# NLOS_PCB.net
KiCad netlist of a schematic drawn in Altium Designer
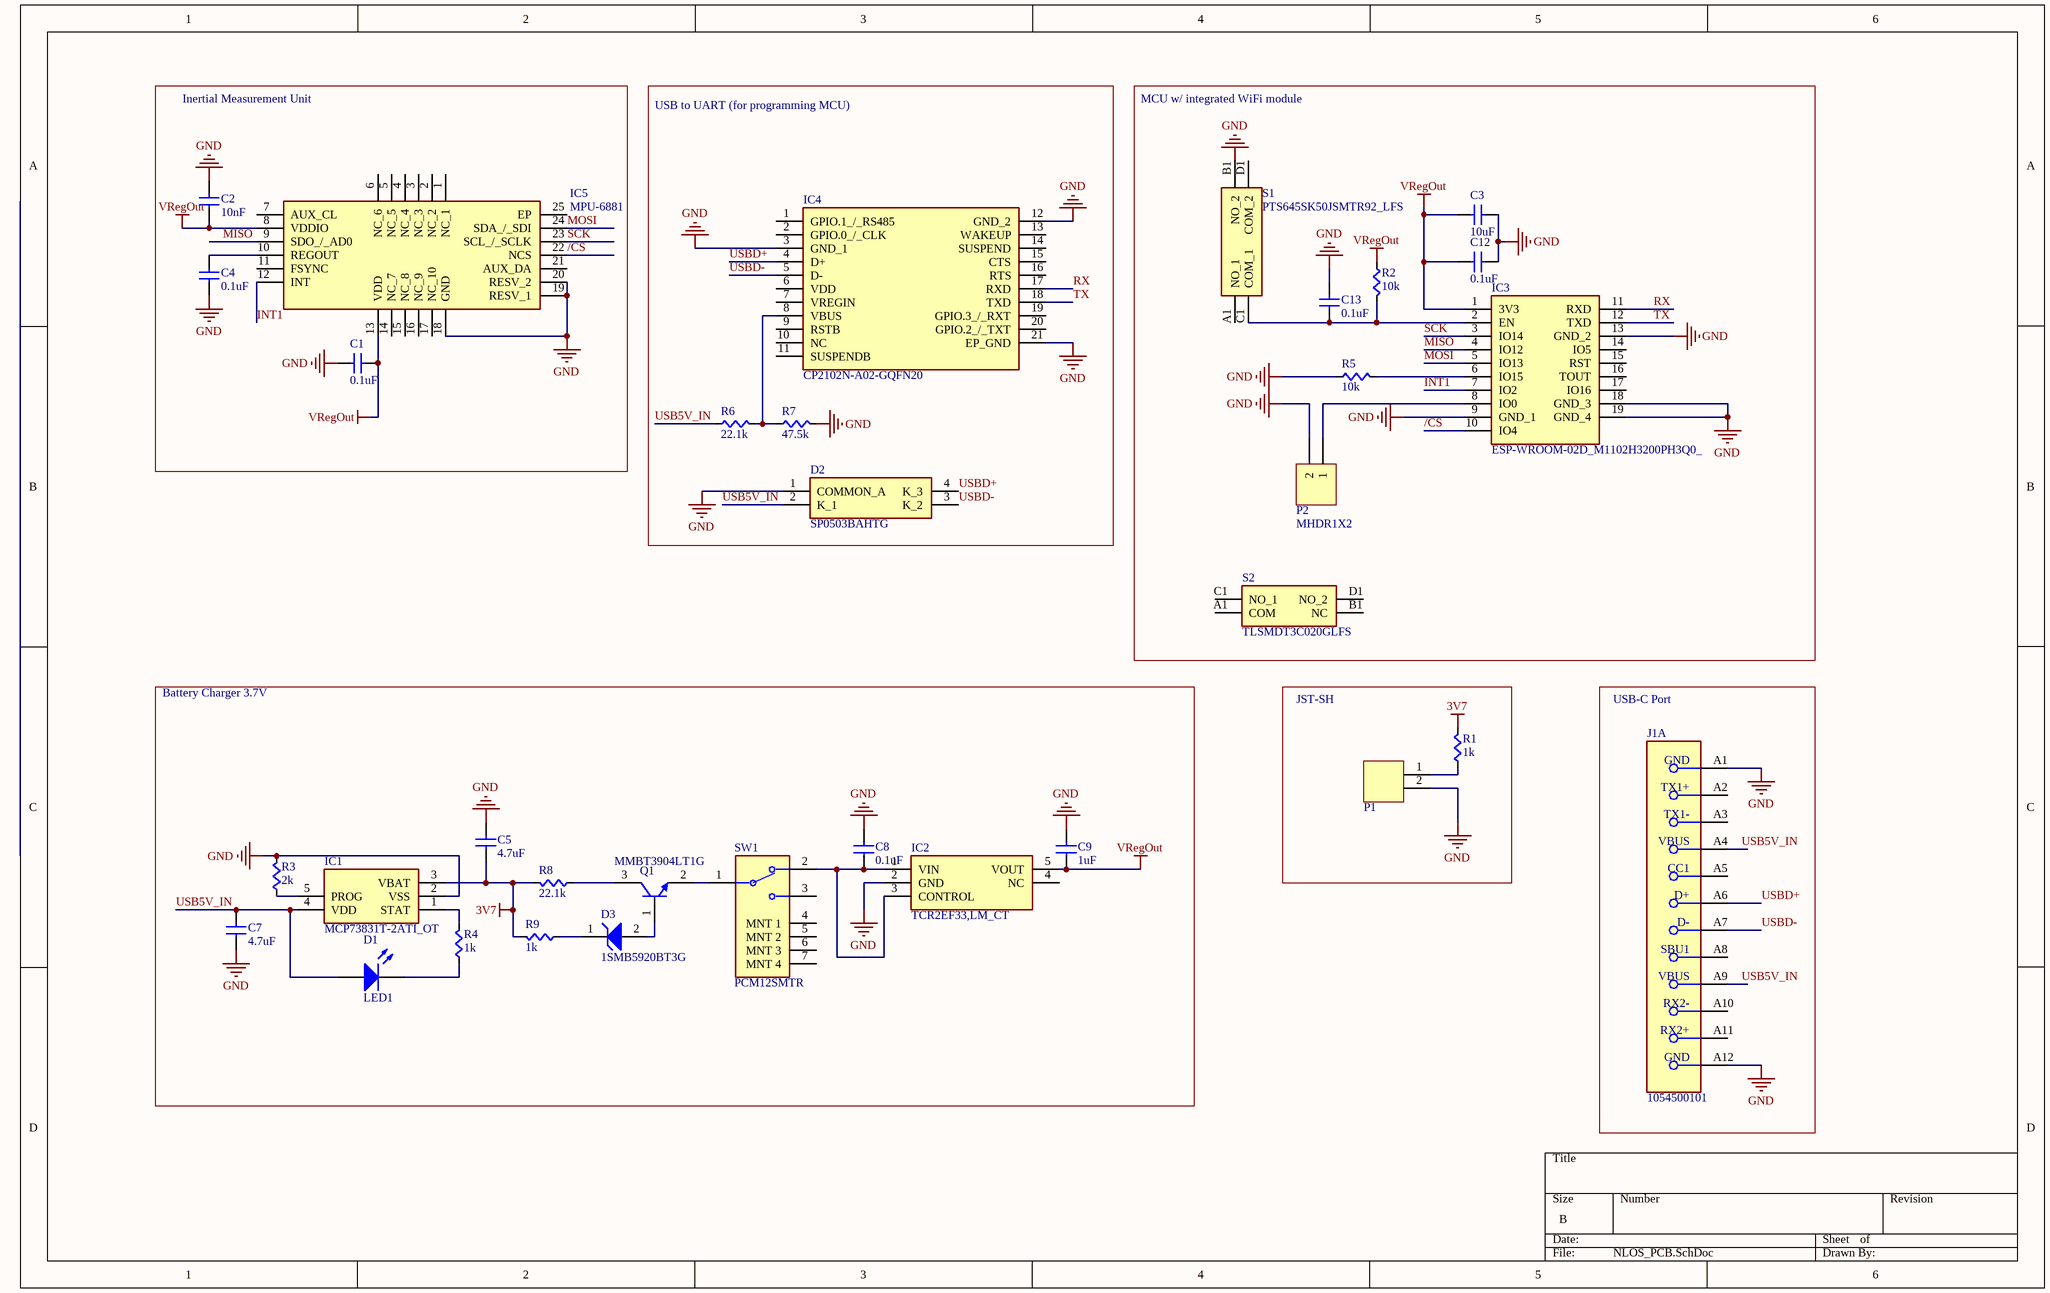
[diagram p0: NLOS_PCB.SchDoc]

(export (version "E")
  (design (tool "Eeschema 10.0.6"))
  (components
    (comp (ref "C1")
      (value "0.1uF")
      (footprint "CAPC0603")
      (fields (field (name "Comment") "Cap"))
      (libsource (lib "Passives") (part "Cap"))
    )
    (comp (ref "C2")
      (value "10nF")
      (footprint "CAPC0603")
      (fields (field (name "Comment") "Cap"))
      (libsource (lib "Passives") (part "Cap"))
    )
    (comp (ref "C3")
      (value "10uF")
      (footprint "CAPC0603")
      (fields (field (name "Comment") "Cap"))
      (libsource (lib "Passives") (part "Cap"))
    )
    (comp (ref "C4")
      (value "0.1uF")
      (footprint "CAPC0603")
      (fields (field (name "Comment") "Cap"))
      (libsource (lib "Passives") (part "Cap"))
    )
    (comp (ref "C5")
      (value "4.7uF")
      (footprint "CAPC0603")
      (fields (field (name "Comment") "Cap"))
      (libsource (lib "Passives") (part "Cap"))
    )
    (comp (ref "C7")
      (value "4.7uF")
      (footprint "CAPC0603")
      (fields (field (name "Comment") "Cap"))
      (libsource (lib "Passives") (part "Cap"))
    )
    (comp (ref "C8")
      (value "0.1uF")
      (footprint "CAPC0603")
      (fields (field (name "Comment") "Cap"))
      (libsource (lib "Passives") (part "Cap"))
    )
    (comp (ref "C9")
      (value "1uF")
      (footprint "CAPC0603")
      (fields (field (name "Comment") "Cap"))
      (libsource (lib "Passives") (part "Cap"))
    )
    (comp (ref "C12")
      (value "0.1uF")
      (footprint "CAPC0603")
      (fields (field (name "Comment") "Cap"))
      (libsource (lib "Passives") (part "Cap"))
    )
    (comp (ref "C13")
      (value "0.1uF")
      (footprint "CAPC0603")
      (fields (field (name "Comment") "Cap"))
      (libsource (lib "Passives") (part "Cap"))
    )
    (comp (ref "D1")
      (value "LED1")
      (footprint "LED-1")
      (description "Typical RED GaAs LED")
      (fields (field (name "PUBLISHER") "Altium Limited"))
      (libsource (lib "Miscellaneous Devices") (part "LED1"))
    )
    (comp (ref "D2")
      (value "SP0503BAHTG")
      (footprint "SamacSys:SP0503BAHTG")
      (description "TVS Diode (Uni-directional)")
      (fields (field (name "MOUSER PART NUMBER") "576-SP0503BAHTG"))
      (libsource (lib "*") (part "SP0503BAHTG"))
    )
    (comp (ref "D3")
      (value "1SMB5920BT3G")
      (footprint "ONSC-SMB-2-403A-03_H_V")
      (description "3 W Zener Voltage Regulator, 2-Pin SMB, Pb-Free, Tape and Reel")
      (fields (field (name "MANUFACTURER") "On Semiconductor"))
      (libsource (lib "Altium Content Vault") (part "ONSC-K1A2-2"))
    )
    (comp (ref "IC1")
      (value "MCP73831T-2ATI_OT")
      (footprint "SamacSys:SOT95P270X145-5N")
      (description "Integrated Circuit")
      (fields
        (field (name "MOUSER2 PART NUMBER") "579-MCP73831T-2ATIOT")
        (field (name "MANUFACTURER_PART_NUMBER") "MCP73831T-2ATI/OT")
      )
      (libsource (lib "*") (part "MCP73831T-2ATI_OT"))
    )
    (comp (ref "IC2")
      (value "TCR2EF33,LM_CT")
      (footprint "SamacSys:SOT-25")
      (description "Integrated Circuit")
      (fields
        (field (name "MOUSER2 PART NUMBER") "757-TCR2EF33LMCT")
        (field (name "MANUFACTURER_PART_NUMBER") "TCR2EF33,LM(CT")
      )
      (libsource (lib "*") (part "TCR2EF33,LM_CT"))
    )
    (comp (ref "IC3")
      (value "ESP-WROOM-02D_M1102H3200PH3Q0_")
      (footprint "SamacSys:ESPWROOM02DM1102H3200PH3Q0")
      (description "Integrated Circuit")
      (fields
        (field (name "MANUFACTURER_PART_NUMBER") "ESP-WROOM-02D(M1102H3200PH3Q0)")
        (field (name "MOUSER PART NUMBER") "356-ESPWROOM02D(4MB)")
      )
      (libsource (lib "*") (part "ESP-WROOM-02D_M1102H3200PH3Q0_"))
    )
    (comp (ref "IC4")
      (value "CP2102N-A02-GQFN20")
      (footprint "SamacSys:CP2102NA02GQFN20")
      (description "Integrated Circuit")
      (fields (field (name "MOUSER PART NUMBER") "634-CP2102NA02GQFN20"))
      (libsource (lib "*") (part "CP2102N-A02-GQFN20"))
    )
    (comp (ref "IC5")
      (value "MPU-6881")
      (footprint "SamacSys:QFN40P300X300X95-25N-D")
      (description "Integrated Circuit")
      (fields (field (name "MOUSER PART NUMBER") "410-MPU-6881"))
      (libsource (lib "*") (part "MPU-6881"))
    )
    (comp (ref "J1")
      (value "1054500101")
      (footprint "FP-1054500101-MFG")
      (description "CONN RCP USB3.1 TYPEC 24P SMD RA")
      (fields
        (field (name "MANUFACTURER") "Molex")
        (field (name "OCTOPART") "https://octopart.com/105450-0101-molex-68082325")
      )
      (libsource (lib "Altium Content Vault") (part "9808b19ecaf079fb99eed69f0495cd0"))
    )
    (comp (ref "P1")
      (value "2-pin Horz Sherlock")
      (footprint "MOLEX-HDR-1X2-SHERLOCK-HORZ")
      (fields
        (field (name "MANUFACTURER PART NUMBER") "0353630260")
        (field (name "MANUFACTURER") "Molex Inc")
      )
      (libsource (lib "Connectors") (part "MOLEX-HDR-1x2-SHERLOCK_RA"))
    )
    (comp (ref "P2")
      (value "MHDR1X2")
      (footprint "MHDR1X2")
      (description "Header, 2-Pin")
      (fields (field (name "PUBLISHER") "Altium Limited"))
      (libsource (lib "Miscellaneous Connectors") (part "MHDR1X2"))
    )
    (comp (ref "Q1")
      (value "MMBT3904LT1G")
      (footprint "ONSC-SOT-23-3-318-08_V")
      (description "General Purpose Transistor, NPN Silicon, 3-Pin SOT-23, Pb-Free, Tape and Reel")
      (fields (field (name "MANUFACTURER") "On Semiconductor"))
      (libsource (lib "Altium Content Vault") (part "ONSC-NPN-B1E2C3-3"))
    )
    (comp (ref "R1")
      (value "1k")
      (footprint "RES0603")
      (fields (field (name "Comment") "Res"))
      (libsource (lib "Passives") (part "Res"))
    )
    (comp (ref "R2")
      (value "10k")
      (footprint "RES0603")
      (fields (field (name "Comment") "Res"))
      (libsource (lib "Passives") (part "Res"))
    )
    (comp (ref "R3")
      (value "2k")
      (footprint "RES0603")
      (fields (field (name "Comment") "Res"))
      (libsource (lib "Passives") (part "Res"))
    )
    (comp (ref "R4")
      (value "1k")
      (footprint "RES0603")
      (fields (field (name "Comment") "Res"))
      (libsource (lib "Passives") (part "Res"))
    )
    (comp (ref "R5")
      (value "10k")
      (footprint "RES0603")
      (fields (field (name "Comment") "Res"))
      (libsource (lib "Passives") (part "Res"))
    )
    (comp (ref "R6")
      (value "22.1k")
      (footprint "RES0603")
      (fields (field (name "Comment") "Res"))
      (libsource (lib "Passives") (part "Res"))
    )
    (comp (ref "R7")
      (value "47.5k")
      (footprint "RES0603")
      (fields (field (name "Comment") "Res"))
      (libsource (lib "Passives") (part "Res"))
    )
    (comp (ref "R8")
      (value "22.1k")
      (footprint "RES0603")
      (fields (field (name "Comment") "Res"))
      (libsource (lib "Passives") (part "Res"))
    )
    (comp (ref "R9")
      (value "1k")
      (footprint "RES0603")
      (fields (field (name "Comment") "Res"))
      (libsource (lib "Passives") (part "Res"))
    )
    (comp (ref "S1")
      (value "PTS645SK50JSMTR92_LFS")
      (footprint "SamacSys:PTS645SK50JSMTR92LFS")
      (description "Switch")
      (fields
        (field (name "MANUFACTURER_PART_NUMBER") "PTS645SK50JSMTR92 LFS")
        (field (name "MOUSER PART NUMBER") "611-SK50JSMTR92LFS")
      )
      (libsource (lib "*") (part "PTS645SK50JSMTR92_LFS"))
    )
    (comp (ref "S2")
      (value "TLSMDT3C020GLFS")
      (footprint "SamacSys:TLSMDT3C020GLFS")
      (description "Tactile Switches 6x6.1x3.45mm Tactile Switch")
      (fields (field (name "MOUSER PART NUMBER") "611-TLSMDT3C020GLFS"))
      (libsource (lib "SamacSys") (part "TLSMDT3C020GLFS"))
    )
    (comp (ref "SW1")
      (value "PCM12SMTR")
      (footprint "FP-PCM12SMTR-MFG")
      (description "SWITCH SLIDE SPDT 300MA 6V")
      (libsource (lib "Altium Content Vault") (part "1a3f67d7e2b5469b171eeab59ffb4d2"))
    )
  )
  (nets
    (net (code "1") (name "/INT1") (class "Default")
      (node (ref "IC3") (pin "7") (pinfunction "IO2_7") (pintype "passive"))
      (node (ref "IC5") (pin "12") (pinfunction "INT_12") (pintype "passive"))
    )
    (net (code "2") (name "/MISO") (class "Default")
      (node (ref "IC3") (pin "4") (pinfunction "IO12_4") (pintype "passive"))
      (node (ref "IC5") (pin "9") (pinfunction "SDO_/_AD0_9") (pintype "passive"))
    )
    (net (code "3") (name "/MOSI") (class "Default")
      (node (ref "IC3") (pin "5") (pinfunction "IO13_5") (pintype "passive"))
      (node (ref "IC5") (pin "24") (pinfunction "SDA_/_SDI_24") (pintype "passive"))
    )
    (net (code "4") (name "/RX") (class "Default")
      (node (ref "IC3") (pin "11") (pinfunction "RXD_11") (pintype "passive"))
      (node (ref "IC4") (pin "17") (pinfunction "RXD_17") (pintype "passive"))
    )
    (net (code "5") (name "/SCK") (class "Default")
      (node (ref "IC3") (pin "3") (pinfunction "IO14_3") (pintype "passive"))
      (node (ref "IC5") (pin "23") (pinfunction "SCL_/_SCLK_23") (pintype "passive"))
    )
    (net (code "6") (name "/TX") (class "Default")
      (node (ref "IC3") (pin "12") (pinfunction "TXD_12") (pintype "passive"))
      (node (ref "IC4") (pin "18") (pinfunction "TXD_18") (pintype "passive"))
    )
    (net (code "7") (name "/USB5V_IN") (class "Default")
      (node (ref "C7") (pin "2") (pinfunction "B_2") (pintype "passive"))
      (node (ref "D1") (pin "1") (pinfunction "A_1") (pintype "passive"))
      (node (ref "D2") (pin "2") (pinfunction "K_1_2") (pintype "passive"))
      (node (ref "IC1") (pin "4") (pinfunction "VDD_4") (pintype "power_in"))
      (node (ref "J1") (pin "A4") (pinfunction "VBUS_A4") (pintype "passive"))
      (node (ref "J1") (pin "A9") (pinfunction "VBUS_A9") (pintype "passive"))
      (node (ref "R6") (pin "2") (pinfunction "B_2") (pintype "passive"))
    )
    (net (code "8") (name "/USBD+") (class "Default")
      (node (ref "D2") (pin "4") (pinfunction "K_3_4") (pintype "passive"))
      (node (ref "IC4") (pin "4") (pinfunction "D+_4") (pintype "passive"))
      (node (ref "J1") (pin "A6") (pinfunction "D+_A6") (pintype "passive"))
    )
    (net (code "9") (name "/USBD-") (class "Default")
      (node (ref "D2") (pin "3") (pinfunction "K_2_3") (pintype "passive"))
      (node (ref "IC4") (pin "5") (pinfunction "D-_5") (pintype "passive"))
      (node (ref "J1") (pin "A7") (pinfunction "D-_A7") (pintype "passive"))
    )
    (net (code "10") (name "/{slash}CS") (class "Default")
      (node (ref "IC3") (pin "10") (pinfunction "IO4_10") (pintype "passive"))
      (node (ref "IC5") (pin "22") (pinfunction "NCS_22") (pintype "passive"))
    )
    (net (code "11") (name "3V7") (class "Default")
      (node (ref "C5") (pin "2") (pinfunction "B_2") (pintype "passive"))
      (node (ref "IC1") (pin "3") (pinfunction "VBAT_3") (pintype "passive"))
      (node (ref "R1") (pin "1") (pinfunction "A_1") (pintype "passive"))
      (node (ref "R8") (pin "1") (pinfunction "A_1") (pintype "passive"))
      (node (ref "R9") (pin "1") (pinfunction "A_1") (pintype "passive"))
    )
    (net (code "12") (name "GND") (class "Default")
      (node (ref "C1") (pin "2") (pinfunction "B_2") (pintype "passive"))
      (node (ref "C12") (pin "1") (pinfunction "A_1") (pintype "passive"))
      (node (ref "C13") (pin "2") (pinfunction "B_2") (pintype "passive"))
      (node (ref "C2") (pin "2") (pinfunction "B_2") (pintype "passive"))
      (node (ref "C3") (pin "1") (pinfunction "A_1") (pintype "passive"))
      (node (ref "C4") (pin "1") (pinfunction "A_1") (pintype "passive"))
      (node (ref "C5") (pin "1") (pinfunction "A_1") (pintype "passive"))
      (node (ref "C7") (pin "1") (pinfunction "A_1") (pintype "passive"))
      (node (ref "C8") (pin "2") (pinfunction "B_2") (pintype "passive"))
      (node (ref "C9") (pin "2") (pinfunction "B_2") (pintype "passive"))
      (node (ref "D2") (pin "1") (pinfunction "COMMON_A_1") (pintype "passive"))
      (node (ref "IC1") (pin "2") (pinfunction "VSS_2") (pintype "power_in"))
      (node (ref "IC2") (pin "2") (pinfunction "GND_2") (pintype "passive"))
      (node (ref "IC3") (pin "13") (pinfunction "GND_2_13") (pintype "passive"))
      (node (ref "IC3") (pin "18") (pinfunction "GND_3_18") (pintype "passive"))
      (node (ref "IC3") (pin "19") (pinfunction "GND_4_19") (pintype "passive"))
      (node (ref "IC3") (pin "9") (pinfunction "GND_1_9") (pintype "passive"))
      (node (ref "IC4") (pin "12") (pinfunction "GND_2_12") (pintype "passive"))
      (node (ref "IC4") (pin "21") (pinfunction "EP_GND_21") (pintype "passive"))
      (node (ref "IC4") (pin "3") (pinfunction "GND_1_3") (pintype "passive"))
      (node (ref "IC5") (pin "18") (pinfunction "GND_18") (pintype "passive"))
      (node (ref "IC5") (pin "19") (pinfunction "RESV_1_19") (pintype "passive"))
      (node (ref "IC5") (pin "20") (pinfunction "RESV_2_20") (pintype "passive"))
      (node (ref "J1") (pin "A1") (pinfunction "GND_A1") (pintype "passive"))
      (node (ref "J1") (pin "A12") (pinfunction "GND_A12") (pintype "passive"))
      (node (ref "P1") (pin "2") (pinfunction "2_2") (pintype "passive"))
      (node (ref "P2") (pin "2") (pinfunction "2_2") (pintype "passive"))
      (node (ref "R3") (pin "1") (pinfunction "A_1") (pintype "passive"))
      (node (ref "R5") (pin "2") (pinfunction "B_2") (pintype "passive"))
      (node (ref "R7") (pin "1") (pinfunction "A_1") (pintype "passive"))
      (node (ref "S1") (pin "B1") (pinfunction "NO_2_B1") (pintype "passive"))
    )
    (net (code "13") (name "Net-(C4-B)") (class "Default")
      (node (ref "C4") (pin "2") (pinfunction "B_2") (pintype "passive"))
      (node (ref "IC5") (pin "10") (pinfunction "REGOUT_10") (pintype "passive"))
    )
    (net (code "14") (name "Net-(C8-A)") (class "Default")
      (node (ref "C8") (pin "1") (pinfunction "A_1") (pintype "passive"))
      (node (ref "IC2") (pin "1") (pinfunction "VIN_1") (pintype "passive"))
      (node (ref "IC2") (pin "3") (pinfunction "CONTROL_3") (pintype "passive"))
      (node (ref "SW1") (pin "2") (pinfunction "2_2") (pintype "passive"))
    )
    (net (code "15") (name "Net-(C13-A)") (class "Default")
      (node (ref "C13") (pin "1") (pinfunction "A_1") (pintype "passive"))
      (node (ref "IC3") (pin "2") (pinfunction "EN_2") (pintype "passive"))
      (node (ref "R2") (pin "1") (pinfunction "A_1") (pintype "passive"))
      (node (ref "S1") (pin "C1") (pinfunction "COM_1_C1") (pintype "passive"))
    )
    (net (code "16") (name "Net-(D1-K)") (class "Default")
      (node (ref "D1") (pin "2") (pinfunction "K_2") (pintype "passive"))
      (node (ref "R4") (pin "2") (pinfunction "B_2") (pintype "passive"))
    )
    (net (code "17") (name "Net-(D3-A)") (class "Default")
      (node (ref "D3") (pin "2") (pinfunction "A_2") (pintype "passive"))
      (node (ref "Q1") (pin "1") (pinfunction "B_1") (pintype "passive"))
    )
    (net (code "18") (name "Net-(D3-K)") (class "Default")
      (node (ref "D3") (pin "1") (pinfunction "K_1") (pintype "passive"))
      (node (ref "R9") (pin "2") (pinfunction "B_2") (pintype "passive"))
    )
    (net (code "19") (name "Net-(IC1-PROG)") (class "Default")
      (node (ref "IC1") (pin "5") (pinfunction "PROG_5") (pintype "passive"))
      (node (ref "R3") (pin "2") (pinfunction "B_2") (pintype "passive"))
    )
    (net (code "20") (name "Net-(IC1-STAT)") (class "Default")
      (node (ref "IC1") (pin "1") (pinfunction "STAT_1") (pintype "passive"))
      (node (ref "R4") (pin "1") (pinfunction "A_1") (pintype "passive"))
    )
    (net (code "21") (name "Net-(IC3-IO0)") (class "Default")
      (node (ref "IC3") (pin "8") (pinfunction "IO0_8") (pintype "passive"))
      (node (ref "P2") (pin "1") (pinfunction "1_1") (pintype "passive"))
    )
    (net (code "22") (name "Net-(IC3-IO15)") (class "Default")
      (node (ref "IC3") (pin "6") (pinfunction "IO15_6") (pintype "passive"))
      (node (ref "R5") (pin "1") (pinfunction "A_1") (pintype "passive"))
    )
    (net (code "23") (name "Net-(IC4-VBUS)") (class "Default")
      (node (ref "IC4") (pin "8") (pinfunction "VBUS_8") (pintype "passive"))
      (node (ref "R6") (pin "1") (pinfunction "A_1") (pintype "passive"))
      (node (ref "R7") (pin "2") (pinfunction "B_2") (pintype "passive"))
    )
    (net (code "24") (name "Net-(Q1-C)") (class "Default")
      (node (ref "Q1") (pin "3") (pinfunction "C_3") (pintype "passive"))
      (node (ref "R8") (pin "2") (pinfunction "B_2") (pintype "passive"))
    )
    (net (code "25") (name "Net-(Q1-E)") (class "Default")
      (node (ref "Q1") (pin "2") (pinfunction "E_2") (pintype "passive"))
      (node (ref "SW1") (pin "1") (pinfunction "1_1") (pintype "passive"))
    )
    (net (code "26") (name "Net-(R1-B)") (class "Default")
      (node (ref "P1") (pin "1") (pinfunction "1_1") (pintype "passive"))
      (node (ref "R1") (pin "2") (pinfunction "B_2") (pintype "passive"))
    )
    (net (code "27") (name "VRegOut") (class "Default")
      (node (ref "C1") (pin "1") (pinfunction "A_1") (pintype "passive"))
      (node (ref "C12") (pin "2") (pinfunction "B_2") (pintype "passive"))
      (node (ref "C2") (pin "1") (pinfunction "A_1") (pintype "passive"))
      (node (ref "C3") (pin "2") (pinfunction "B_2") (pintype "passive"))
      (node (ref "C9") (pin "1") (pinfunction "A_1") (pintype "passive"))
      (node (ref "IC2") (pin "5") (pinfunction "VOUT_5") (pintype "passive"))
      (node (ref "IC3") (pin "1") (pinfunction "3V3_1") (pintype "passive"))
      (node (ref "IC5") (pin "13") (pinfunction "VDD_13") (pintype "passive"))
      (node (ref "IC5") (pin "8") (pinfunction "VDDIO_8") (pintype "passive"))
      (node (ref "R2") (pin "2") (pinfunction "B_2") (pintype "passive"))
    )
    (net (code "28") (name "unconnected-(IC2-NC-Pad4)") (class "Default")
      (node (ref "IC2") (pin "4") (pinfunction "NC_4") (pintype "passive"))
    )
    (net (code "29") (name "unconnected-(IC3-IO5-Pad14)") (class "Default")
      (node (ref "IC3") (pin "14") (pinfunction "IO5_14") (pintype "passive"))
    )
    (net (code "30") (name "unconnected-(IC3-IO16-Pad17)") (class "Default")
      (node (ref "IC3") (pin "17") (pinfunction "IO16_17") (pintype "passive"))
    )
    (net (code "31") (name "unconnected-(IC3-RST-Pad15)") (class "Default")
      (node (ref "IC3") (pin "15") (pinfunction "RST_15") (pintype "passive"))
    )
    (net (code "32") (name "unconnected-(IC3-TOUT-Pad16)") (class "Default")
      (node (ref "IC3") (pin "16") (pinfunction "TOUT_16") (pintype "passive"))
    )
    (net (code "33") (name "unconnected-(IC4-CTS-Pad15)") (class "Default")
      (node (ref "IC4") (pin "15") (pinfunction "CTS_15") (pintype "passive"))
    )
    (net (code "34") (name "unconnected-(IC4-GPIO.0_{slash}_CLK-Pad2)") (class "Default")
      (node (ref "IC4") (pin "2") (pinfunction "GPIO.0_/_CLK_2") (pintype "passive"))
    )
    (net (code "35") (name "unconnected-(IC4-GPIO.1_{slash}_RS485-Pad1)") (class "Default")
      (node (ref "IC4") (pin "1") (pinfunction "GPIO.1_/_RS485_1") (pintype "passive"))
    )
    (net (code "36") (name "unconnected-(IC4-GPIO.2_{slash}_TXT-Pad20)") (class "Default")
      (node (ref "IC4") (pin "20") (pinfunction "GPIO.2_/_TXT_20") (pintype "passive"))
    )
    (net (code "37") (name "unconnected-(IC4-GPIO.3_{slash}_RXT-Pad19)") (class "Default")
      (node (ref "IC4") (pin "19") (pinfunction "GPIO.3_/_RXT_19") (pintype "passive"))
    )
    (net (code "38") (name "unconnected-(IC4-NC-Pad10)") (class "Default")
      (node (ref "IC4") (pin "10") (pinfunction "NC_10") (pintype "passive"))
    )
    (net (code "39") (name "unconnected-(IC4-RSTB-Pad9)") (class "Default")
      (node (ref "IC4") (pin "9") (pinfunction "RSTB_9") (pintype "passive"))
    )
    (net (code "40") (name "unconnected-(IC4-RTS-Pad16)") (class "Default")
      (node (ref "IC4") (pin "16") (pinfunction "RTS_16") (pintype "passive"))
    )
    (net (code "41") (name "unconnected-(IC4-SUSPEND-Pad14)") (class "Default")
      (node (ref "IC4") (pin "14") (pinfunction "SUSPEND_14") (pintype "passive"))
    )
    (net (code "42") (name "unconnected-(IC4-SUSPENDB-Pad11)") (class "Default")
      (node (ref "IC4") (pin "11") (pinfunction "SUSPENDB_11") (pintype "passive"))
    )
    (net (code "43") (name "unconnected-(IC4-VDD-Pad6)") (class "Default")
      (node (ref "IC4") (pin "6") (pinfunction "VDD_6") (pintype "passive"))
    )
    (net (code "44") (name "unconnected-(IC4-VREGIN-Pad7)") (class "Default")
      (node (ref "IC4") (pin "7") (pinfunction "VREGIN_7") (pintype "passive"))
    )
    (net (code "45") (name "unconnected-(IC4-WAKEUP-Pad13)") (class "Default")
      (node (ref "IC4") (pin "13") (pinfunction "WAKEUP_13") (pintype "passive"))
    )
    (net (code "46") (name "unconnected-(IC5-AUX_CL-Pad7)") (class "Default")
      (node (ref "IC5") (pin "7") (pinfunction "AUX_CL_7") (pintype "passive"))
    )
    (net (code "47") (name "unconnected-(IC5-AUX_DA-Pad21)") (class "Default")
      (node (ref "IC5") (pin "21") (pinfunction "AUX_DA_21") (pintype "passive"))
    )
    (net (code "48") (name "unconnected-(IC5-EP-Pad25)") (class "Default")
      (node (ref "IC5") (pin "25") (pinfunction "EP_25") (pintype "passive"))
    )
    (net (code "49") (name "unconnected-(IC5-FSYNC-Pad11)") (class "Default")
      (node (ref "IC5") (pin "11") (pinfunction "FSYNC_11") (pintype "passive"))
    )
    (net (code "50") (name "unconnected-(IC5-NC_1-Pad1)") (class "Default")
      (node (ref "IC5") (pin "1") (pinfunction "NC_1_1") (pintype "passive"))
    )
    (net (code "51") (name "unconnected-(IC5-NC_2-Pad2)") (class "Default")
      (node (ref "IC5") (pin "2") (pinfunction "NC_2_2") (pintype "passive"))
    )
    (net (code "52") (name "unconnected-(IC5-NC_3-Pad3)") (class "Default")
      (node (ref "IC5") (pin "3") (pinfunction "NC_3_3") (pintype "passive"))
    )
    (net (code "53") (name "unconnected-(IC5-NC_4-Pad4)") (class "Default")
      (node (ref "IC5") (pin "4") (pinfunction "NC_4_4") (pintype "passive"))
    )
    (net (code "54") (name "unconnected-(IC5-NC_5-Pad5)") (class "Default")
      (node (ref "IC5") (pin "5") (pinfunction "NC_5_5") (pintype "passive"))
    )
    (net (code "55") (name "unconnected-(IC5-NC_6-Pad6)") (class "Default")
      (node (ref "IC5") (pin "6") (pinfunction "NC_6_6") (pintype "passive"))
    )
    (net (code "56") (name "unconnected-(IC5-NC_7-Pad14)") (class "Default")
      (node (ref "IC5") (pin "14") (pinfunction "NC_7_14") (pintype "passive"))
    )
    (net (code "57") (name "unconnected-(IC5-NC_8-Pad15)") (class "Default")
      (node (ref "IC5") (pin "15") (pinfunction "NC_8_15") (pintype "passive"))
    )
    (net (code "58") (name "unconnected-(IC5-NC_9-Pad16)") (class "Default")
      (node (ref "IC5") (pin "16") (pinfunction "NC_9_16") (pintype "passive"))
    )
    (net (code "59") (name "unconnected-(IC5-NC_10-Pad17)") (class "Default")
      (node (ref "IC5") (pin "17") (pinfunction "NC_10_17") (pintype "passive"))
    )
    (net (code "60") (name "unconnected-(J1A-CC1-PadA5)") (class "Default")
      (node (ref "J1") (pin "A5") (pinfunction "CC1_A5") (pintype "passive"))
    )
    (net (code "61") (name "unconnected-(J1A-RX2+-PadA11)") (class "Default")
      (node (ref "J1") (pin "A11") (pinfunction "RX2+_A11") (pintype "passive"))
    )
    (net (code "62") (name "unconnected-(J1A-RX2--PadA10)") (class "Default")
      (node (ref "J1") (pin "A10") (pinfunction "RX2-_A10") (pintype "passive"))
    )
    (net (code "63") (name "unconnected-(J1A-SBU1-PadA8)") (class "Default")
      (node (ref "J1") (pin "A8") (pinfunction "SBU1_A8") (pintype "passive"))
    )
    (net (code "64") (name "unconnected-(J1A-TX1+-PadA2)") (class "Default")
      (node (ref "J1") (pin "A2") (pinfunction "TX1+_A2") (pintype "passive"))
    )
    (net (code "65") (name "unconnected-(J1A-TX1--PadA3)") (class "Default")
      (node (ref "J1") (pin "A3") (pinfunction "TX1-_A3") (pintype "passive"))
    )
    (net (code "66") (name "unconnected-(S1-COM_2-PadD1)") (class "Default")
      (node (ref "S1") (pin "D1") (pinfunction "COM_2_D1") (pintype "passive"))
    )
    (net (code "67") (name "unconnected-(S1-NO_1-PadA1)") (class "Default")
      (node (ref "S1") (pin "A1") (pinfunction "NO_1_A1") (pintype "passive"))
    )
    (net (code "68") (name "unconnected-(S2-COM-PadA1)") (class "Default")
      (node (ref "S2") (pin "A1") (pinfunction "COM_A1") (pintype "passive"))
    )
    (net (code "69") (name "unconnected-(S2-NC-PadB1)") (class "Default")
      (node (ref "S2") (pin "B1") (pinfunction "NC_B1") (pintype "passive"))
    )
    (net (code "70") (name "unconnected-(S2-NO_1-PadC1)") (class "Default")
      (node (ref "S2") (pin "C1") (pinfunction "NO_1_C1") (pintype "passive"))
    )
    (net (code "71") (name "unconnected-(S2-NO_2-PadD1)") (class "Default")
      (node (ref "S2") (pin "D1") (pinfunction "NO_2_D1") (pintype "passive"))
    )
    (net (code "72") (name "unconnected-(SW1-MNT_1-Pad4)") (class "Default")
      (node (ref "SW1") (pin "4") (pinfunction "MNT_1_4") (pintype "passive"))
    )
    (net (code "73") (name "unconnected-(SW1-MNT_2-Pad5)") (class "Default")
      (node (ref "SW1") (pin "5") (pinfunction "MNT_2_5") (pintype "passive"))
    )
    (net (code "74") (name "unconnected-(SW1-MNT_3-Pad6)") (class "Default")
      (node (ref "SW1") (pin "6") (pinfunction "MNT_3_6") (pintype "passive"))
    )
    (net (code "75") (name "unconnected-(SW1-MNT_4-Pad7)") (class "Default")
      (node (ref "SW1") (pin "7") (pinfunction "MNT_4_7") (pintype "passive"))
    )
    (net (code "76") (name "unconnected-(SW1-Pad3)") (class "Default")
      (node (ref "SW1") (pin "3") (pinfunction "3_3") (pintype "passive"))
    )
  )
)
